# Stepper_Driver_Sheet2.net
KiCad netlist of a schematic drawn in Altium Designer
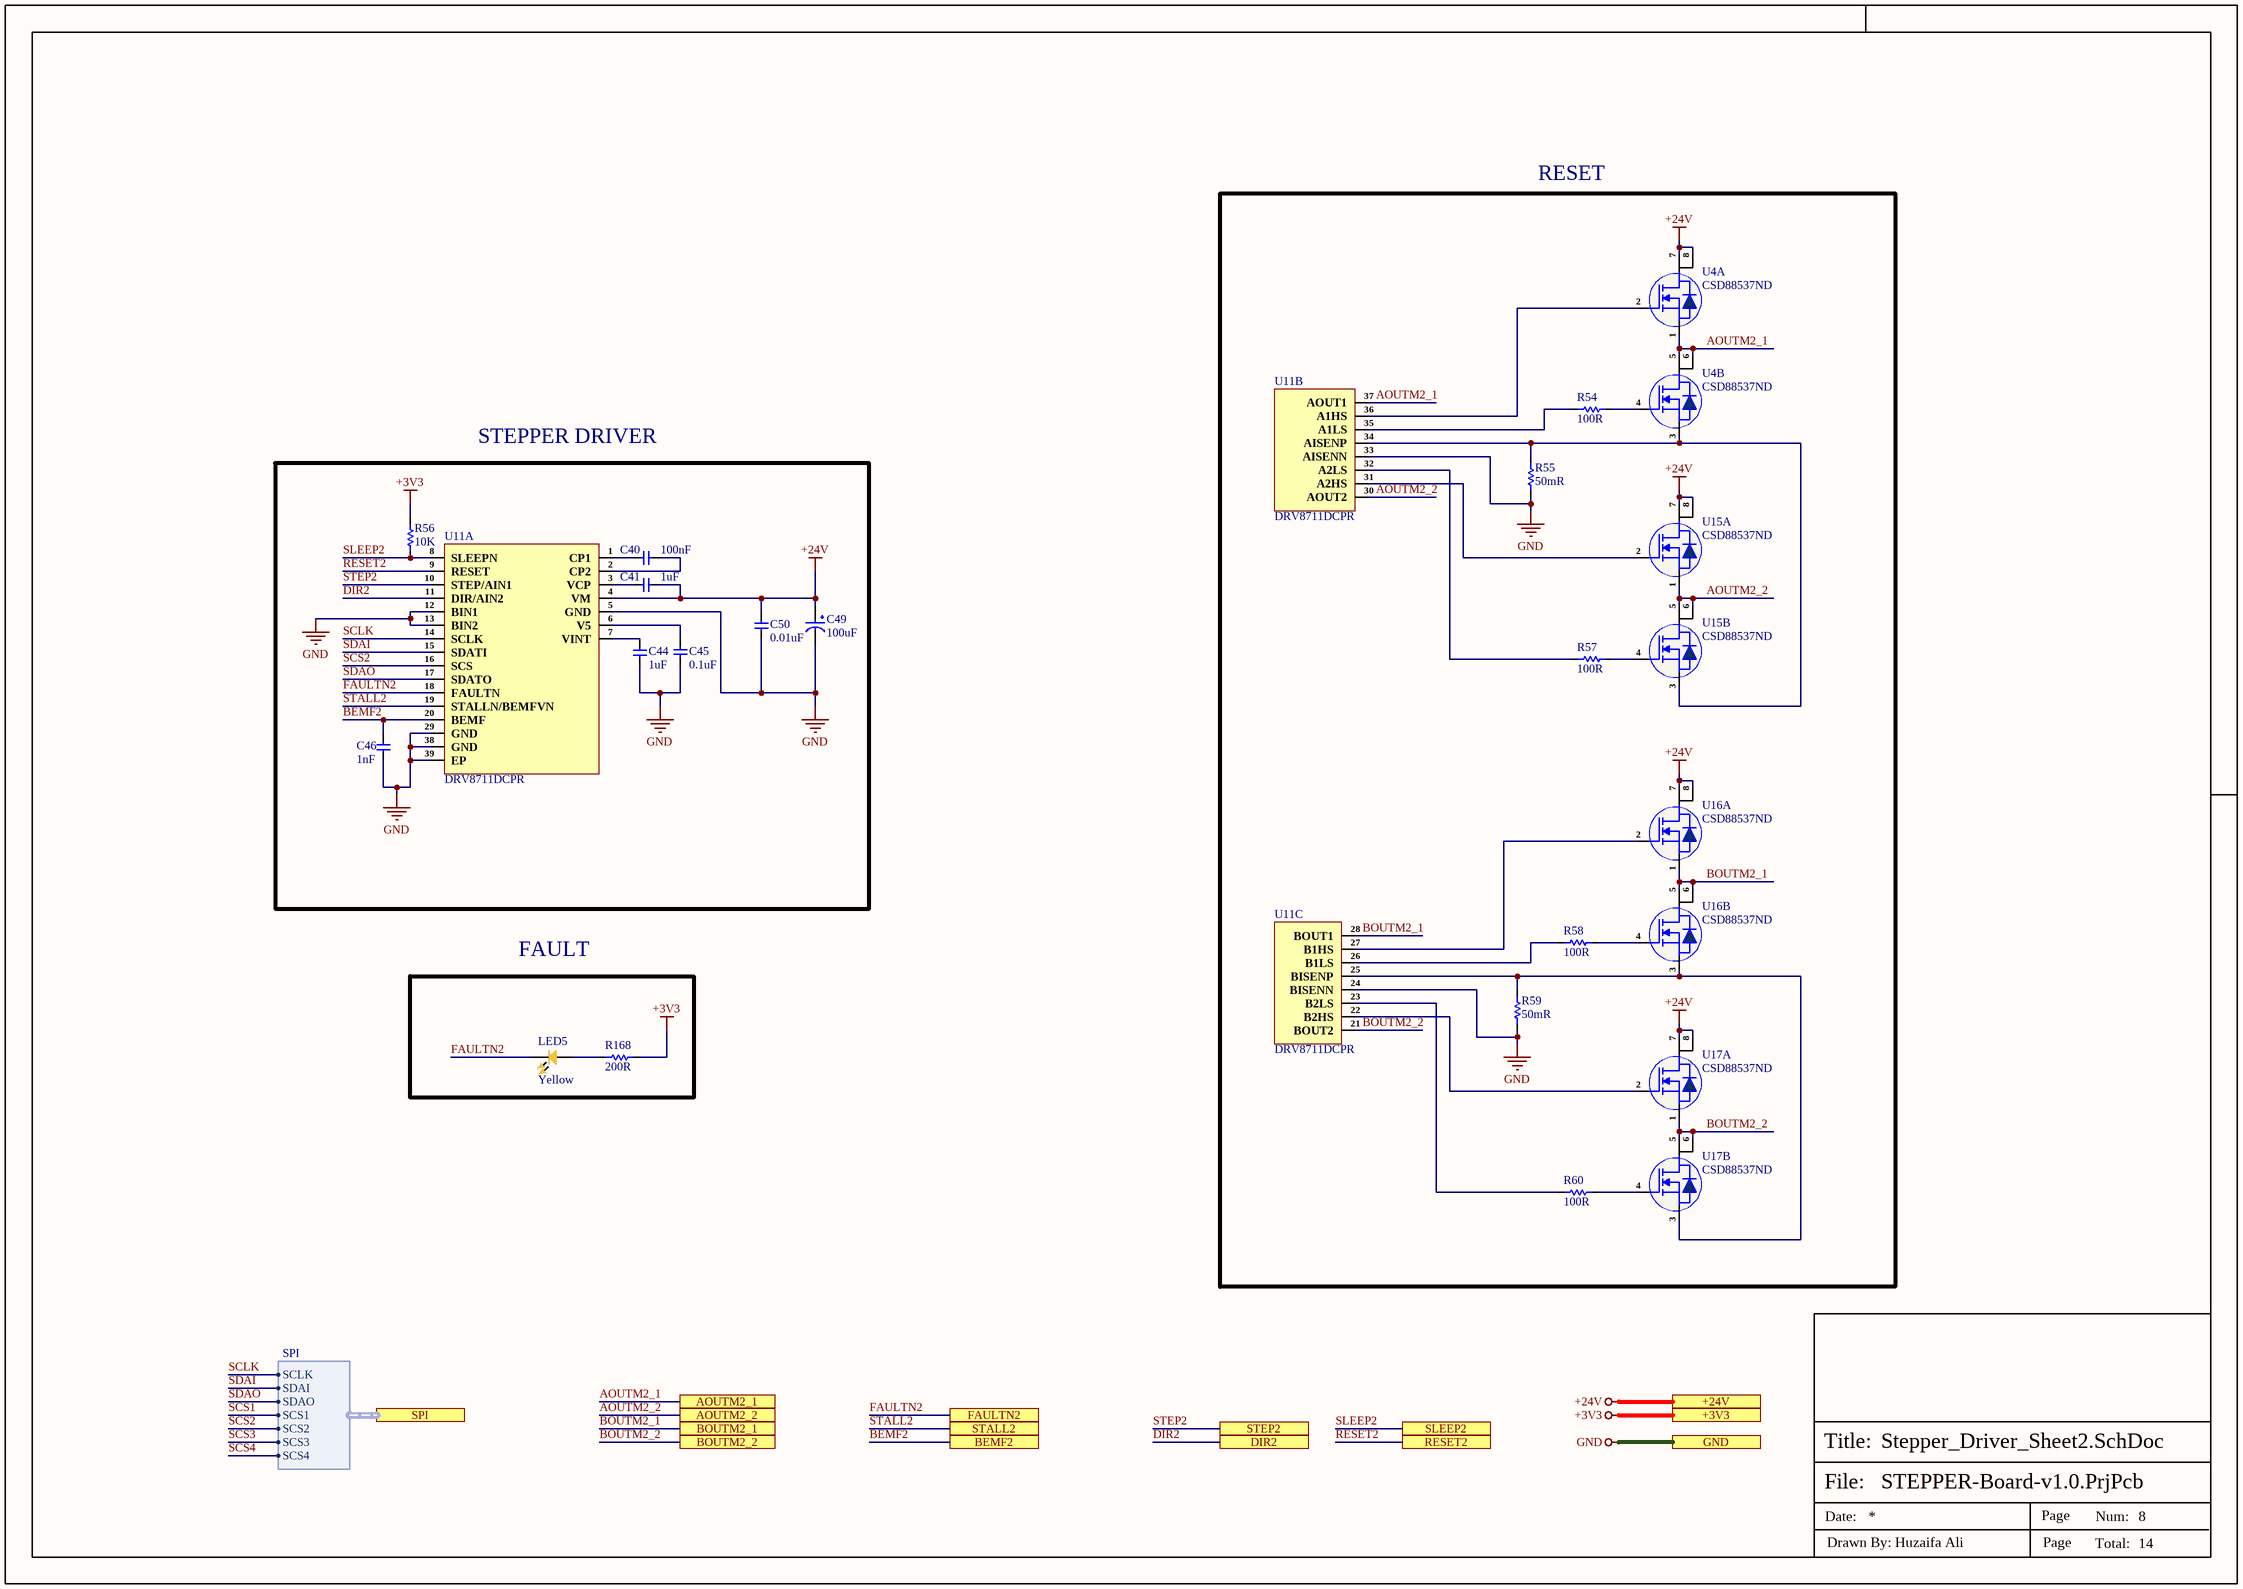
[diagram p0: Stepper_Driver_Sheet2.SchDoc]

(export (version "E")
  (design (tool "Eeschema 10.0.6"))
  (components
    (comp (ref "C40")
      (value "100nF")
      (footprint "cap-0402")
      (description "CAP CER 0.1UF 50V X7R 0402")
      (fields
        (field (name "MANUFACTURER") "TDK")
        (field (name "MANUFACTURER PART NUMBER") "C1005X7R1H104KT000F")
      )
      (libsource (lib "eSpark Libraries") (part "C1005X7R1H104KT000F"))
    )
    (comp (ref "C41")
      (value "1uF")
      (footprint "Cap-0402")
      (description "CAP CER 1UF 10V X5R 0402")
      (fields
        (field (name "MANUFACTURER") "Yageo")
        (field (name "MANUFACTURER PART NUMBER") "CC0402KRX5R6BB105")
      )
      (libsource (lib "eSpark Libraries") (part "CC0402KRX5R6BB105"))
    )
    (comp (ref "C44")
      (value "1uF")
      (footprint "Cap-0402")
      (description "CAP CER 1UF 10V X5R 0402")
      (fields
        (field (name "MANUFACTURER") "Yageo")
        (field (name "MANUFACTURER PART NUMBER") "CC0402KRX5R6BB105")
      )
      (libsource (lib "eSpark Libraries") (part "CC0402KRX5R6BB105"))
    )
    (comp (ref "C45")
      (value "0.1uF")
      (footprint "Cap-0402")
      (description "CAP CER 0.1UF 16V X7R 0402")
      (fields
        (field (name "MANUFACTURER") "Yageo")
        (field (name "MANUFACTURER PART NUMBER") "CC0402JRX7R7BB104")
      )
      (libsource (lib "eSpark Libraries") (part "CC0402JRX7R7BB104"))
    )
    (comp (ref "C46")
      (value "1nF")
      (footprint "Cap-0402")
      (description "CAP CER 1000PF 25V C0G 0402")
      (fields
        (field (name "MANUFACTURER") "TDK")
        (field (name "MANUFACTURER PART NUMBER") "C1005C0G1E102JT000F")
      )
      (libsource (lib "eSpark Libraries") (part "C1005C0G1E102JT000F"))
    )
    (comp (ref "C49")
      (value "100uF")
      (footprint "UWT1H101MNL1GS_")
      (description "CAP ALUM 100UF 20% 50V SMD")
      (fields
        (field (name "MANUFACTURER") "Nichicon")
        (field (name "MANUFACTURER PART NUMBER") "UWT1H101MNL1GS")
      )
      (libsource (lib "eSpark Libraries") (part "UWT1H101MNL1GS"))
    )
    (comp (ref "C50")
      (value "0.01uF")
      (footprint "Cap-0603")
      (description "CAP CER 10000PF 50V C0G/NP0 0603")
      (fields
        (field (name "MANUFACTURER") "Murata")
        (field (name "MANUFACTURER PART NUMBER") "GRM1885C1H103JA01D")
      )
      (libsource (lib "eSpark Libraries") (part "GRM1885C1H103JA01D"))
    )
    (comp (ref "LED5")
      (value "Yellow")
      (footprint "LED-0603")
      (description "yellow 0603 Light Emitting Diodes (LED) ROHS")
      (fields
        (field (name "MANUFACTURER") "Foshan NationStar Optoelectronics")
        (field (name "MANUFACTURER PART NUMBER") "NCD0603Y2")
      )
      (libsource (lib "eSpark Libraries") (part "NCD0603Y2"))
    )
    (comp (ref "R54")
      (value "100R")
      (footprint "Res-0402")
      (description "RES 100 OHM 1% 1/16W 0402")
      (fields
        (field (name "MANUFACTURER") "Yageo")
        (field (name "MANUFACTURER PART NUMBER") "RC0402FR-07100RL")
      )
      (libsource (lib "eSpark Libraries") (part "RC0402FR-07100RL"))
    )
    (comp (ref "R55")
      (value "50mR")
      (footprint "RES-2010")
      (fields
        (field (name "MANUFACTURER") "TA-I Tech")
        (field (name "MANUFACTURER PART NUMBER") "RLM20FECR050")
        (field (name "LCSC PART NUMBER") "C912938")
      )
      (libsource (lib "eSpark Libraries") (part "RLM20FECR050"))
    )
    (comp (ref "R56")
      (value "10K")
      (footprint "Res-0402")
      (description "RES 10K OHM 1% 1/16W 0402")
      (fields
        (field (name "MANUFACTURER") "Yageo")
        (field (name "MANUFACTURER PART NUMBER") "RC0402FR-0710KL")
      )
      (libsource (lib "eSpark Libraries") (part "RC0402FR-0710KL"))
    )
    (comp (ref "R57")
      (value "100R")
      (footprint "Res-0402")
      (description "RES 100 OHM 1% 1/16W 0402")
      (fields
        (field (name "MANUFACTURER") "Yageo")
        (field (name "MANUFACTURER PART NUMBER") "RC0402FR-07100RL")
      )
      (libsource (lib "eSpark Libraries") (part "RC0402FR-07100RL"))
    )
    (comp (ref "R58")
      (value "100R")
      (footprint "Res-0402")
      (description "RES 100 OHM 1% 1/16W 0402")
      (fields
        (field (name "MANUFACTURER") "Yageo")
        (field (name "MANUFACTURER PART NUMBER") "RC0402FR-07100RL")
      )
      (libsource (lib "eSpark Libraries") (part "RC0402FR-07100RL"))
    )
    (comp (ref "R59")
      (value "50mR")
      (footprint "RES-2010")
      (fields
        (field (name "MANUFACTURER") "TA-I Tech")
        (field (name "MANUFACTURER PART NUMBER") "RLM20FECR050")
        (field (name "LCSC PART NUMBER") "C912938")
      )
      (libsource (lib "eSpark Libraries") (part "RLM20FECR050"))
    )
    (comp (ref "R60")
      (value "100R")
      (footprint "Res-0402")
      (description "RES 100 OHM 1% 1/16W 0402")
      (fields
        (field (name "MANUFACTURER") "Yageo")
        (field (name "MANUFACTURER PART NUMBER") "RC0402FR-07100RL")
      )
      (libsource (lib "eSpark Libraries") (part "RC0402FR-07100RL"))
    )
    (comp (ref "R168")
      (value "200R")
      (footprint "Res-0402")
      (description "RES 200 OHM 1% 1/16W 0402")
      (fields
        (field (name "MANUFACTURER") "Yageo")
        (field (name "MANUFACTURER PART NUMBER") "RC0402FR-07200RL")
      )
      (libsource (lib "eSpark Libraries") (part "RC0402FR-07200RL"))
    )
    (comp (ref "U4")
      (value "CSD88537ND")
      (footprint "SOIC-8")
      (description "MOSFET 2N-CH 60V 15A 8SOIC")
      (fields (field (name "LCSC PART NUMBER") "C117439") (field (name "MANUFACTURER") "Texas Instruments"))
      (libsource (lib "eSpark Libraries") (part "CSD88537ND"))
    )
    (comp (ref "U11")
      (value "DRV8711DCPR")
      (footprint "HTSSOP-38-EP-4.4mm")
      (description "IC MTR DRV BIPOLR 8-52V 38HTSSOP")
      (fields (field (name "LCSC PART NUMBER") "C60013") (field (name "MANUFACTURER") "Texas Instruments"))
      (libsource (lib "eSpark Libraries") (part "DRV8711DCPR"))
    )
    (comp (ref "U15")
      (value "CSD88537ND")
      (footprint "SOIC-8")
      (description "MOSFET 2N-CH 60V 15A 8SOIC")
      (fields (field (name "LCSC PART NUMBER") "C117439") (field (name "MANUFACTURER") "Texas Instruments"))
      (libsource (lib "eSpark Libraries") (part "CSD88537ND"))
    )
    (comp (ref "U16")
      (value "CSD88537ND")
      (footprint "SOIC-8")
      (description "MOSFET 2N-CH 60V 15A 8SOIC")
      (fields (field (name "LCSC PART NUMBER") "C117439") (field (name "MANUFACTURER") "Texas Instruments"))
      (libsource (lib "eSpark Libraries") (part "CSD88537ND"))
    )
    (comp (ref "U17")
      (value "CSD88537ND")
      (footprint "SOIC-8")
      (description "MOSFET 2N-CH 60V 15A 8SOIC")
      (fields (field (name "LCSC PART NUMBER") "C117439") (field (name "MANUFACTURER") "Texas Instruments"))
      (libsource (lib "eSpark Libraries") (part "CSD88537ND"))
    )
  )
  (nets
    (net (code "2") (name "+3V3") (class "Default")
      (node (ref "R168") (pin "2") (pinfunction "2_2") (pintype "passive"))
      (node (ref "R56") (pin "1") (pinfunction "1_1") (pintype "passive"))
    )
    (net (code "3") (name "+24V") (class "Default")
      (node (ref "C41") (pin "2") (pinfunction "2_2") (pintype "passive"))
      (node (ref "C49") (pin "1") (pinfunction "1_1") (pintype "passive"))
      (node (ref "C50") (pin "2") (pinfunction "2_2") (pintype "passive"))
      (node (ref "U11") (pin "4") (pinfunction "VM_4") (pintype "passive"))
      (node (ref "U15") (pin "7") (pinfunction "D1_7") (pintype "passive"))
      (node (ref "U15") (pin "8") (pinfunction "D1_8") (pintype "passive"))
      (node (ref "U16") (pin "7") (pinfunction "D1_7") (pintype "passive"))
      (node (ref "U16") (pin "8") (pinfunction "D1_8") (pintype "passive"))
      (node (ref "U17") (pin "7") (pinfunction "D1_7") (pintype "passive"))
      (node (ref "U17") (pin "8") (pinfunction "D1_8") (pintype "passive"))
      (node (ref "U4") (pin "7") (pinfunction "D1_7") (pintype "passive"))
      (node (ref "U4") (pin "8") (pinfunction "D1_8") (pintype "passive"))
    )
    (net (code "4") (name "/AOUTM2_1") (class "Default")
      (node (ref "U11") (pin "37") (pinfunction "AOUT1_37") (pintype "passive"))
      (node (ref "U4") (pin "1") (pinfunction "S1_1") (pintype "passive"))
      (node (ref "U4") (pin "5") (pinfunction "D2_5") (pintype "passive"))
      (node (ref "U4") (pin "6") (pinfunction "D2_6") (pintype "passive"))
    )
    (net (code "5") (name "/AOUTM2_2") (class "Default")
      (node (ref "U11") (pin "30") (pinfunction "AOUT2_30") (pintype "passive"))
      (node (ref "U15") (pin "1") (pinfunction "S1_1") (pintype "passive"))
      (node (ref "U15") (pin "5") (pinfunction "D2_5") (pintype "passive"))
      (node (ref "U15") (pin "6") (pinfunction "D2_6") (pintype "passive"))
    )
    (net (code "6") (name "/BEMF2") (class "Default")
      (node (ref "C46") (pin "2") (pinfunction "2_2") (pintype "passive"))
      (node (ref "U11") (pin "20") (pinfunction "BEMF_20") (pintype "passive"))
    )
    (net (code "7") (name "/BOUTM2_1") (class "Default")
      (node (ref "U11") (pin "28") (pinfunction "BOUT1_28") (pintype "passive"))
      (node (ref "U16") (pin "1") (pinfunction "S1_1") (pintype "passive"))
      (node (ref "U16") (pin "5") (pinfunction "D2_5") (pintype "passive"))
      (node (ref "U16") (pin "6") (pinfunction "D2_6") (pintype "passive"))
    )
    (net (code "8") (name "/BOUTM2_2") (class "Default")
      (node (ref "U11") (pin "21") (pinfunction "BOUT2_21") (pintype "passive"))
      (node (ref "U17") (pin "1") (pinfunction "S1_1") (pintype "passive"))
      (node (ref "U17") (pin "5") (pinfunction "D2_5") (pintype "passive"))
      (node (ref "U17") (pin "6") (pinfunction "D2_6") (pintype "passive"))
    )
    (net (code "9") (name "/DIR2") (class "Default")
      (node (ref "U11") (pin "11") (pinfunction "DIR/AIN2_11") (pintype "passive"))
    )
    (net (code "10") (name "/FAULTN2") (class "Default")
      (node (ref "LED5") (pin "2") (pinfunction "2_2") (pintype "passive"))
      (node (ref "U11") (pin "18") (pinfunction "FAULTN_18") (pintype "passive"))
    )
    (net (code "11") (name "/RESET2") (class "Default")
      (node (ref "U11") (pin "9") (pinfunction "RESET_9") (pintype "passive"))
    )
    (net (code "12") (name "/SCLK") (class "Default")
      (node (ref "U11") (pin "14") (pinfunction "SCLK_14") (pintype "passive"))
    )
    (net (code "14") (name "/SCS2") (class "Default")
      (node (ref "U11") (pin "16") (pinfunction "SCS_16") (pintype "passive"))
    )
    (net (code "17") (name "/SDAI") (class "Default")
      (node (ref "U11") (pin "15") (pinfunction "SDATI_15") (pintype "passive"))
    )
    (net (code "18") (name "/SDAO") (class "Default")
      (node (ref "U11") (pin "17") (pinfunction "SDATO_17") (pintype "passive"))
    )
    (net (code "19") (name "/SLEEP2") (class "Default")
      (node (ref "R56") (pin "2") (pinfunction "2_2") (pintype "passive"))
      (node (ref "U11") (pin "8") (pinfunction "SLEEPN_8") (pintype "passive"))
    )
    (net (code "20") (name "/STALL2") (class "Default")
      (node (ref "U11") (pin "19") (pinfunction "STALLN/BEMFVN_19") (pintype "passive"))
    )
    (net (code "21") (name "/STEP2") (class "Default")
      (node (ref "U11") (pin "10") (pinfunction "STEP/AIN1_10") (pintype "passive"))
    )
    (net (code "23") (name "GND") (class "Default")
      (node (ref "C44") (pin "1") (pinfunction "1_1") (pintype "passive"))
      (node (ref "C45") (pin "2") (pinfunction "2_2") (pintype "passive"))
      (node (ref "C46") (pin "1") (pinfunction "1_1") (pintype "passive"))
      (node (ref "C49") (pin "2") (pinfunction "2_2") (pintype "passive"))
      (node (ref "C50") (pin "1") (pinfunction "1_1") (pintype "passive"))
      (node (ref "R55") (pin "1") (pinfunction "1_1") (pintype "passive"))
      (node (ref "R59") (pin "1") (pinfunction "1_1") (pintype "passive"))
      (node (ref "U11") (pin "12") (pinfunction "BIN1_12") (pintype "passive"))
      (node (ref "U11") (pin "13") (pinfunction "BIN2_13") (pintype "passive"))
      (node (ref "U11") (pin "24") (pinfunction "BISENN_24") (pintype "passive"))
      (node (ref "U11") (pin "29") (pinfunction "GND_29") (pintype "passive"))
      (node (ref "U11") (pin "33") (pinfunction "AISENN_33") (pintype "passive"))
      (node (ref "U11") (pin "38") (pinfunction "GND_38") (pintype "passive"))
      (node (ref "U11") (pin "39") (pinfunction "EP_39") (pintype "passive"))
      (node (ref "U11") (pin "5") (pinfunction "GND_5") (pintype "passive"))
    )
    (net (code "24") (name "Net-(LED5-Pad1)") (class "Default")
      (node (ref "LED5") (pin "1") (pinfunction "1_1") (pintype "passive"))
      (node (ref "R168") (pin "1") (pinfunction "1_1") (pintype "passive"))
    )
    (net (code "25") (name "Net-(U4B-G4)") (class "Default")
      (node (ref "R54") (pin "2") (pinfunction "2_2") (pintype "passive"))
      (node (ref "U4") (pin "4") (pinfunction "G4_4") (pintype "passive"))
    )
    (net (code "26") (name "Net-(U11A-CP1)") (class "Default")
      (node (ref "C40") (pin "1") (pinfunction "1_1") (pintype "passive"))
      (node (ref "U11") (pin "1") (pinfunction "CP1_1") (pintype "passive"))
    )
    (net (code "27") (name "Net-(U11A-CP2)") (class "Default")
      (node (ref "C40") (pin "2") (pinfunction "2_2") (pintype "passive"))
      (node (ref "U11") (pin "2") (pinfunction "CP2_2") (pintype "passive"))
    )
    (net (code "28") (name "Net-(U11A-V5)") (class "Default")
      (node (ref "C45") (pin "1") (pinfunction "1_1") (pintype "passive"))
      (node (ref "U11") (pin "6") (pinfunction "V5_6") (pintype "passive"))
    )
    (net (code "29") (name "Net-(U11A-VCP)") (class "Default")
      (node (ref "C41") (pin "1") (pinfunction "1_1") (pintype "passive"))
      (node (ref "U11") (pin "3") (pinfunction "VCP_3") (pintype "passive"))
    )
    (net (code "30") (name "Net-(U11A-VINT)") (class "Default")
      (node (ref "C44") (pin "2") (pinfunction "2_2") (pintype "passive"))
      (node (ref "U11") (pin "7") (pinfunction "VINT_7") (pintype "passive"))
    )
    (net (code "31") (name "Net-(U11B-A1HS)") (class "Default")
      (node (ref "U11") (pin "36") (pinfunction "A1HS_36") (pintype "passive"))
      (node (ref "U4") (pin "2") (pinfunction "G1_2") (pintype "passive"))
    )
    (net (code "32") (name "Net-(U11B-A1LS)") (class "Default")
      (node (ref "R54") (pin "1") (pinfunction "1_1") (pintype "passive"))
      (node (ref "U11") (pin "35") (pinfunction "A1LS_35") (pintype "passive"))
    )
    (net (code "33") (name "Net-(U11B-A2HS)") (class "Default")
      (node (ref "U11") (pin "31") (pinfunction "A2HS_31") (pintype "passive"))
      (node (ref "U15") (pin "2") (pinfunction "G1_2") (pintype "passive"))
    )
    (net (code "34") (name "Net-(U11B-A2LS)") (class "Default")
      (node (ref "R57") (pin "1") (pinfunction "1_1") (pintype "passive"))
      (node (ref "U11") (pin "32") (pinfunction "A2LS_32") (pintype "passive"))
    )
    (net (code "35") (name "Net-(U11B-AISENP)") (class "Default")
      (node (ref "R55") (pin "2") (pinfunction "2_2") (pintype "passive"))
      (node (ref "U11") (pin "34") (pinfunction "AISENP_34") (pintype "passive"))
      (node (ref "U15") (pin "3") (pinfunction "S2_3") (pintype "passive"))
      (node (ref "U4") (pin "3") (pinfunction "S2_3") (pintype "passive"))
    )
    (net (code "36") (name "Net-(U11C-B1HS)") (class "Default")
      (node (ref "U11") (pin "27") (pinfunction "B1HS_27") (pintype "passive"))
      (node (ref "U16") (pin "2") (pinfunction "G1_2") (pintype "passive"))
    )
    (net (code "37") (name "Net-(U11C-B1LS)") (class "Default")
      (node (ref "R58") (pin "1") (pinfunction "1_1") (pintype "passive"))
      (node (ref "U11") (pin "26") (pinfunction "B1LS_26") (pintype "passive"))
    )
    (net (code "38") (name "Net-(U11C-B2HS)") (class "Default")
      (node (ref "U11") (pin "22") (pinfunction "B2HS_22") (pintype "passive"))
      (node (ref "U17") (pin "2") (pinfunction "G1_2") (pintype "passive"))
    )
    (net (code "39") (name "Net-(U11C-B2LS)") (class "Default")
      (node (ref "R60") (pin "1") (pinfunction "1_1") (pintype "passive"))
      (node (ref "U11") (pin "23") (pinfunction "B2LS_23") (pintype "passive"))
    )
    (net (code "40") (name "Net-(U11C-BISENP)") (class "Default")
      (node (ref "R59") (pin "2") (pinfunction "2_2") (pintype "passive"))
      (node (ref "U11") (pin "25") (pinfunction "BISENP_25") (pintype "passive"))
      (node (ref "U16") (pin "3") (pinfunction "S2_3") (pintype "passive"))
      (node (ref "U17") (pin "3") (pinfunction "S2_3") (pintype "passive"))
    )
    (net (code "41") (name "Net-(U15B-G4)") (class "Default")
      (node (ref "R57") (pin "2") (pinfunction "2_2") (pintype "passive"))
      (node (ref "U15") (pin "4") (pinfunction "G4_4") (pintype "passive"))
    )
    (net (code "42") (name "Net-(U16B-G4)") (class "Default")
      (node (ref "R58") (pin "2") (pinfunction "2_2") (pintype "passive"))
      (node (ref "U16") (pin "4") (pinfunction "G4_4") (pintype "passive"))
    )
    (net (code "43") (name "Net-(U17B-G4)") (class "Default")
      (node (ref "R60") (pin "2") (pinfunction "2_2") (pintype "passive"))
      (node (ref "U17") (pin "4") (pinfunction "G4_4") (pintype "passive"))
    )
  )
)
